# Capteur_ToF.net
KiCad netlist of a schematic drawn in EAGLE
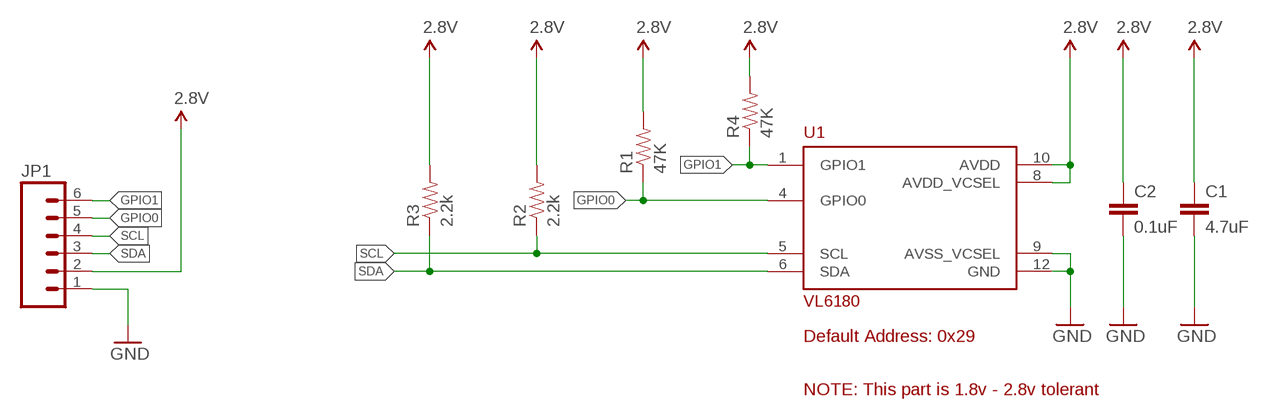
[diagram p0: schematic, sheet 1]

(export (version "E")
  (design (tool "Eeschema 10.0.6"))
  (components
    (comp (ref "C1")
      (value "4.7uF")
      (footprint "eagle-import:0603-CAP")
      (libsource (lib "eagle-import") (part "4.7UF-6.3V-10%(0603)0603"))
    )
    (comp (ref "C2")
      (value "0.1uF")
      (footprint "eagle-import:0603-CAP")
      (libsource (lib "eagle-import") (part "0.1UF-25V(+80/-20%)(0603)"))
    )
    (comp (ref "JP1")
      (value "M06SIP")
      (footprint "eagle-import:1X06")
      (libsource (lib "eagle-import") (part "M06SIP"))
    )
    (comp (ref "R1")
      (value "47K")
      (footprint "eagle-import:0603-RES")
      (libsource (lib "eagle-import") (part "47KOHM1/10W1%(0603)"))
    )
    (comp (ref "R2")
      (value "2.2k")
      (footprint "eagle-import:0603-RES")
      (libsource (lib "eagle-import") (part "2.2KOHM1/10W1%(0603)"))
    )
    (comp (ref "R3")
      (value "2.2k")
      (footprint "eagle-import:0603-RES")
      (libsource (lib "eagle-import") (part "2.2KOHM1/10W1%(0603)"))
    )
    (comp (ref "R4")
      (value "47K")
      (footprint "eagle-import:0603-RES")
      (libsource (lib "eagle-import") (part "47KOHM1/10W1%(0603)"))
    )
    (comp (ref "U1")
      (value "VL6180")
      (footprint "eagle-import:VL6180")
      (libsource (lib "eagle-import") (part "VL6180"))
    )
  )
  (nets
    (net (code "1") (name "2.8V") (class "Default")
      (node (ref "C1") (pin "1") (pinfunction "1_1") (pintype "passive"))
      (node (ref "C2") (pin "1") (pinfunction "1_1") (pintype "passive"))
      (node (ref "JP1") (pin "2") (pinfunction "2_2") (pintype "passive"))
      (node (ref "R1") (pin "2") (pinfunction "2_2") (pintype "passive"))
      (node (ref "R2") (pin "2") (pinfunction "2_2") (pintype "passive"))
      (node (ref "R3") (pin "2") (pinfunction "2_2") (pintype "passive"))
      (node (ref "R4") (pin "2") (pinfunction "2_2") (pintype "passive"))
      (node (ref "U1") (pin "10") (pinfunction "AVDD_10") (pintype "bidirectional"))
      (node (ref "U1") (pin "8") (pinfunction "AVDD_VCSEL_8") (pintype "bidirectional"))
    )
    (net (code "2") (name "GND") (class "Default")
      (node (ref "C1") (pin "2") (pinfunction "2_2") (pintype "passive"))
      (node (ref "C2") (pin "2") (pinfunction "2_2") (pintype "passive"))
      (node (ref "JP1") (pin "1") (pinfunction "1_1") (pintype "passive"))
      (node (ref "U1") (pin "12") (pinfunction "GND_12") (pintype "bidirectional"))
      (node (ref "U1") (pin "9") (pinfunction "AVSS_VCSEL_9") (pintype "bidirectional"))
    )
    (net (code "3") (name "GPIO0") (class "Default")
      (node (ref "JP1") (pin "5") (pinfunction "5_5") (pintype "passive"))
      (node (ref "R1") (pin "1") (pinfunction "1_1") (pintype "passive"))
      (node (ref "U1") (pin "4") (pinfunction "GPIO0_4") (pintype "bidirectional"))
    )
    (net (code "4") (name "GPIO1") (class "Default")
      (node (ref "JP1") (pin "6") (pinfunction "6_6") (pintype "passive"))
      (node (ref "R4") (pin "1") (pinfunction "1_1") (pintype "passive"))
      (node (ref "U1") (pin "1") (pinfunction "GPIO1_1") (pintype "bidirectional"))
    )
    (net (code "5") (name "SCL") (class "Default")
      (node (ref "JP1") (pin "4") (pinfunction "4_4") (pintype "passive"))
      (node (ref "R2") (pin "1") (pinfunction "1_1") (pintype "passive"))
      (node (ref "U1") (pin "5") (pinfunction "SCL_5") (pintype "bidirectional"))
    )
    (net (code "6") (name "SDA") (class "Default")
      (node (ref "JP1") (pin "3") (pinfunction "3_3") (pintype "passive"))
      (node (ref "R3") (pin "1") (pinfunction "1_1") (pintype "passive"))
      (node (ref "U1") (pin "6") (pinfunction "SDA_6") (pintype "bidirectional"))
    )
  )
)
